# Sensors.net
KiCad netlist of a schematic drawn in Altium Designer
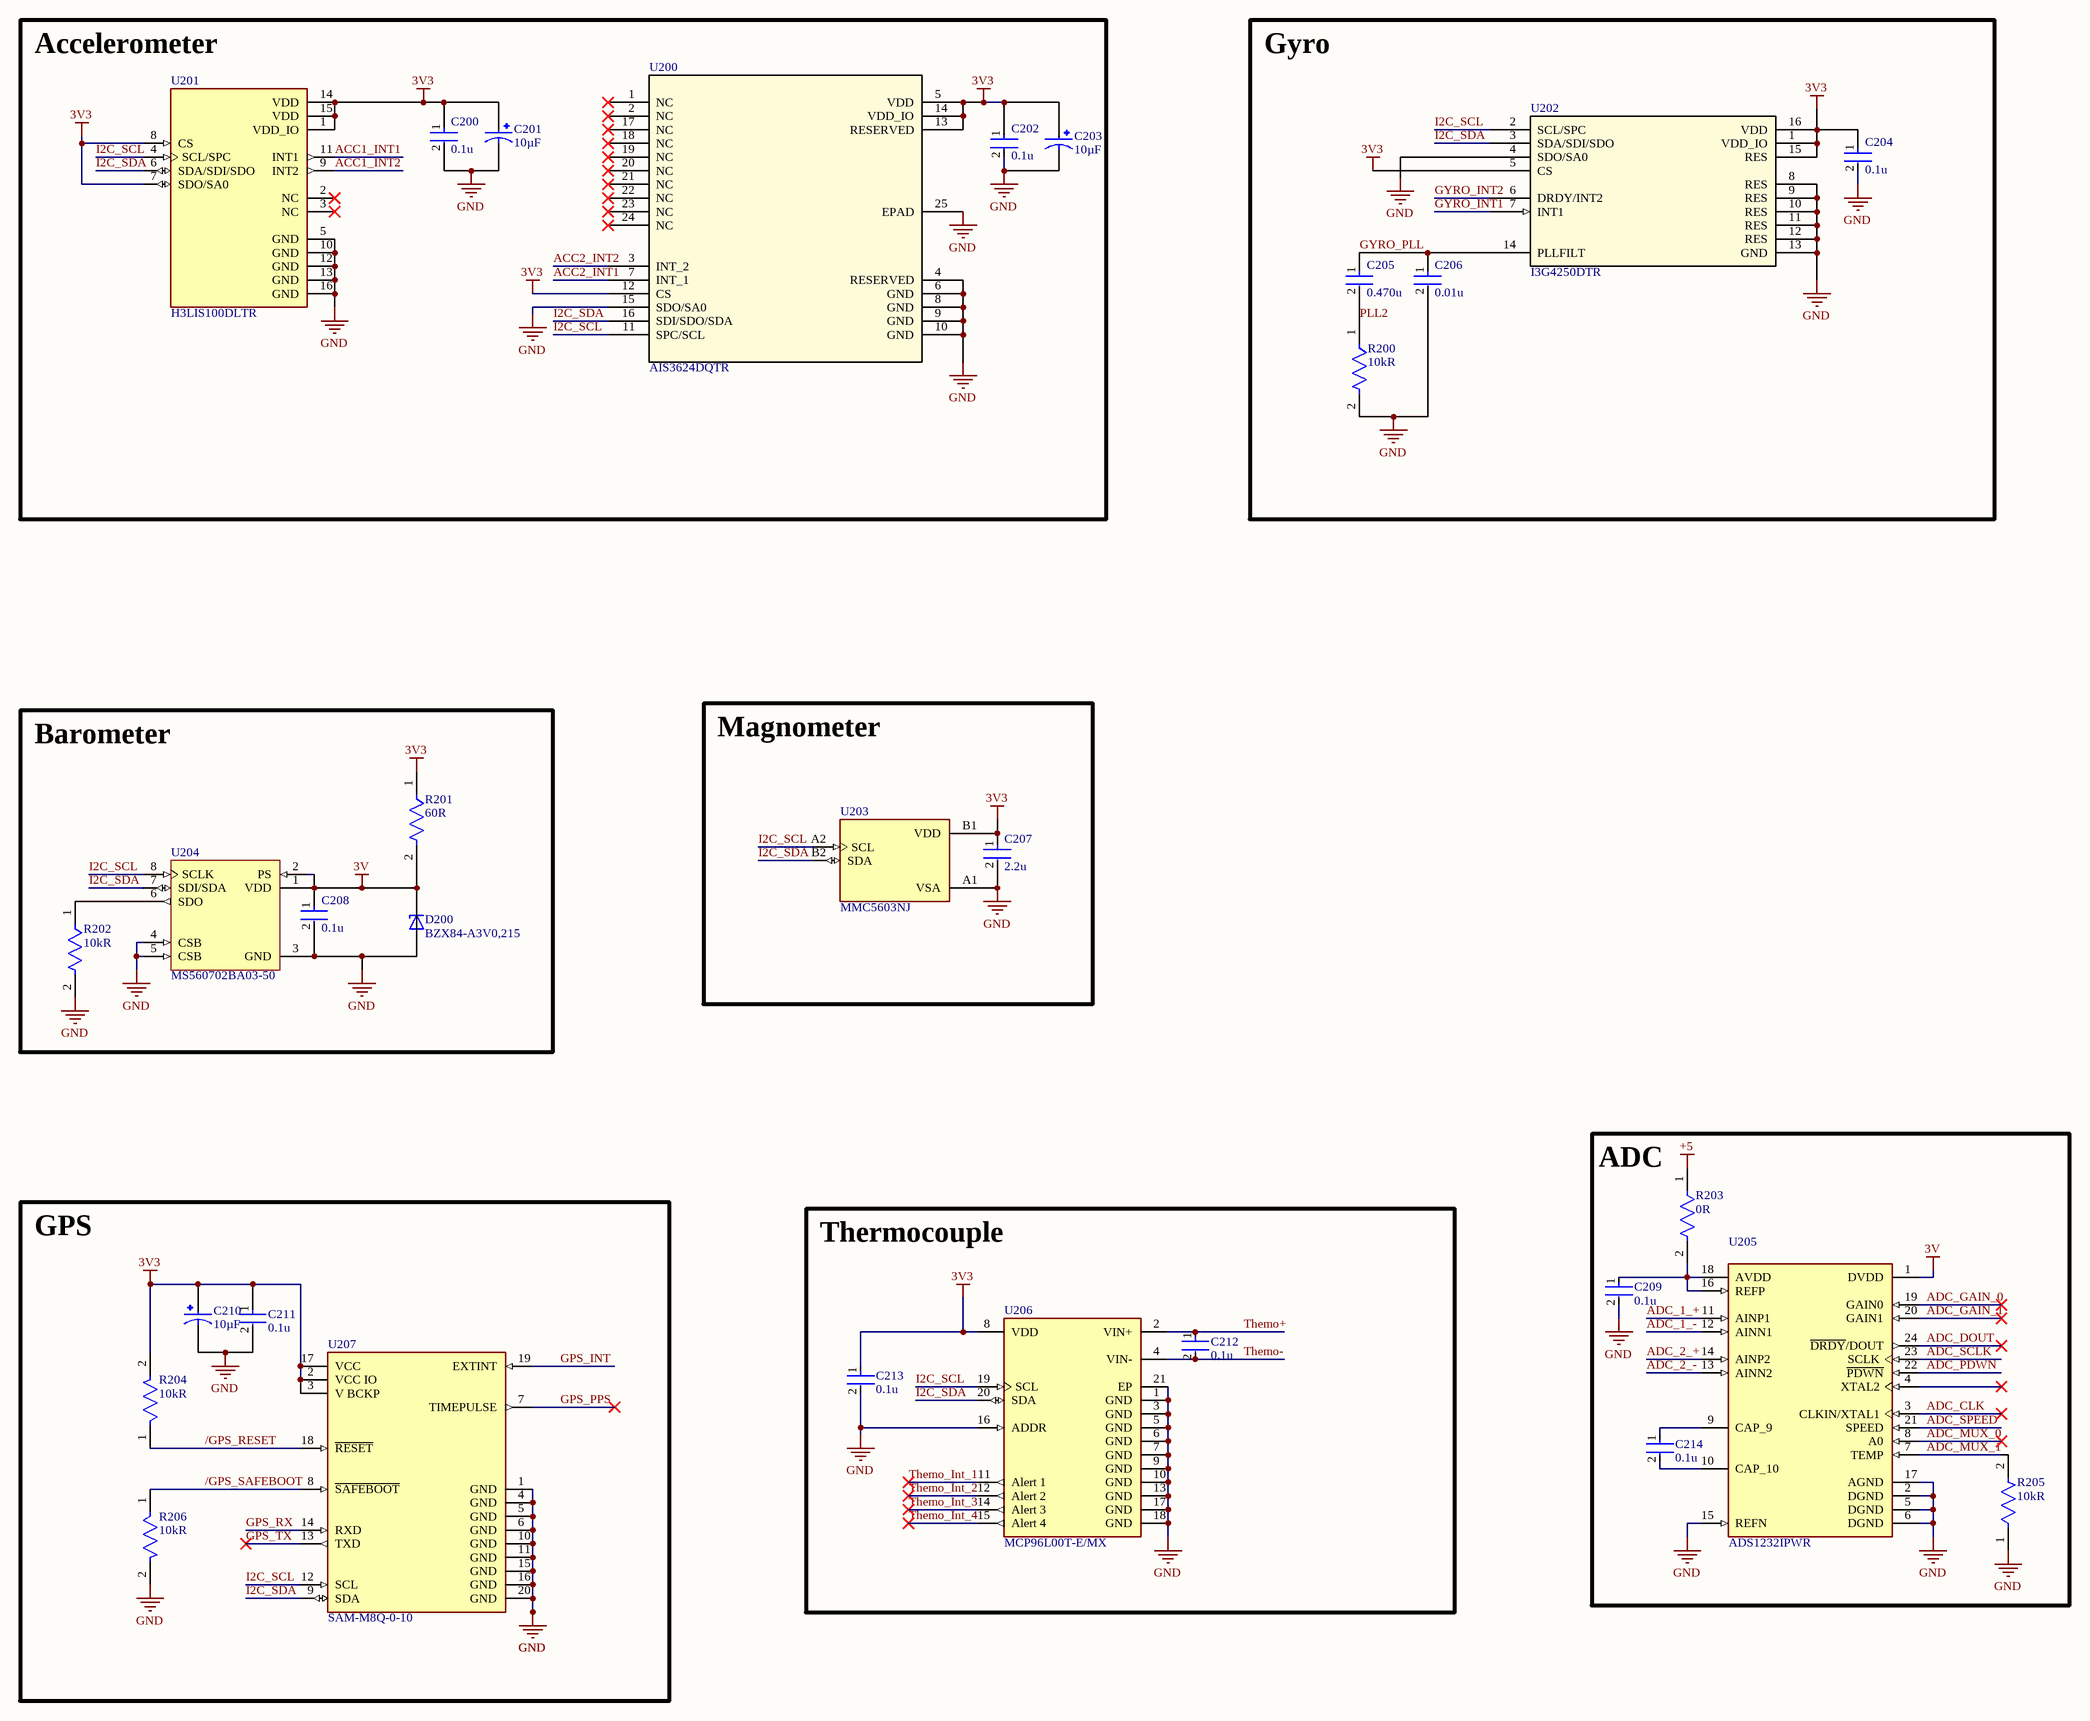
[diagram p0: Sensors.SchDoc]

(export (version "E")
  (design (tool "Eeschema 10.0.6"))
  (components
    (comp (ref "C200")
      (value "CL10C681JB8NFNC")
      (footprint "FP-CL10-IPC_A")
      (description "Cap Ceramic 680pF 50V C0G ±5% Pad SMD 0603 +125°C T/R")
      (fields (field (name "CAPACITANCE") "0.1u") (field (name "TOLERANCE") "5%"))
      (libsource (lib "Altium Content Vault") (part "b4654b650e69147ec39a6b967a45e02"))
    )
    (comp (ref "C201")
      (value "10µF")
      (footprint "CAP_EEEFN1C100R")
      (description "10ÂµF 16V Aluminum Electrolytic Capacitors Radial, Can - SMD 1.35Ohm @ 100kHz 2000 Hrs @ 105Â°C")
      (fields (field (name "DIGI-KEY_PART_NUMBER") "10-EEE-FN1C100RCT-ND") (field (name "MP") "EEEFN1C100R"))
      (libsource (lib "") (part "EEEFN1C100R_1"))
    )
    (comp (ref "C202")
      (value "CL10C681JB8NFNC")
      (footprint "FP-CL10-IPC_A")
      (description "Cap Ceramic 680pF 50V C0G ±5% Pad SMD 0603 +125°C T/R")
      (fields (field (name "CAPACITANCE") "0.1u") (field (name "TOLERANCE") "5%"))
      (libsource (lib "Altium Content Vault") (part "b4654b650e69147ec39a6b967a45e02"))
    )
    (comp (ref "C203")
      (value "10µF")
      (footprint "CAP_EEEFN1C100R")
      (description "10ÂµF 16V Aluminum Electrolytic Capacitors Radial, Can - SMD 1.35Ohm @ 100kHz 2000 Hrs @ 105Â°C")
      (fields (field (name "DIGI-KEY_PART_NUMBER") "10-EEE-FN1C100RCT-ND") (field (name "MP") "EEEFN1C100R"))
      (libsource (lib "") (part "EEEFN1C100R_1"))
    )
    (comp (ref "C204")
      (value "CL10C681JB8NFNC")
      (footprint "FP-CL10-IPC_A")
      (description "Cap Ceramic 680pF 50V C0G ±5% Pad SMD 0603 +125°C T/R")
      (fields (field (name "CAPACITANCE") "0.1u") (field (name "TOLERANCE") "5%"))
      (libsource (lib "Altium Content Vault") (part "b4654b650e69147ec39a6b967a45e02"))
    )
    (comp (ref "C205")
      (value "CL10C681JB8NFNC")
      (footprint "FP-CL10-IPC_A")
      (description "Cap Ceramic 680pF 50V C0G ±5% Pad SMD 0603 +125°C T/R")
      (fields (field (name "CAPACITANCE") "0.470u") (field (name "TOLERANCE") "5%"))
      (libsource (lib "Altium Content Vault") (part "b4654b650e69147ec39a6b967a45e02"))
    )
    (comp (ref "C206")
      (value "CL10C681JB8NFNC")
      (footprint "FP-CL10-IPC_A")
      (description "Cap Ceramic 680pF 50V C0G ±5% Pad SMD 0603 +125°C T/R")
      (fields (field (name "CAPACITANCE") "0.01u") (field (name "TOLERANCE") "5%"))
      (libsource (lib "Altium Content Vault") (part "b4654b650e69147ec39a6b967a45e02"))
    )
    (comp (ref "C207")
      (value "CL10C681JB8NFNC")
      (footprint "FP-CL10-IPC_A")
      (description "Cap Ceramic 680pF 50V C0G ±5% Pad SMD 0603 +125°C T/R")
      (fields (field (name "CAPACITANCE") "2.2u") (field (name "TOLERANCE") "5%"))
      (libsource (lib "Altium Content Vault") (part "b4654b650e69147ec39a6b967a45e02"))
    )
    (comp (ref "C208")
      (value "CL10C681JB8NFNC")
      (footprint "FP-CL10-IPC_A")
      (description "Cap Ceramic 680pF 50V C0G ±5% Pad SMD 0603 +125°C T/R")
      (fields (field (name "CAPACITANCE") "0.1u") (field (name "TOLERANCE") "5%"))
      (libsource (lib "Altium Content Vault") (part "b4654b650e69147ec39a6b967a45e02"))
    )
    (comp (ref "C209")
      (value "CL10C681JB8NFNC")
      (footprint "FP-CL10-IPC_A")
      (description "Cap Ceramic 680pF 50V C0G ±5% Pad SMD 0603 +125°C T/R")
      (fields (field (name "CAPACITANCE") "0.1u") (field (name "TOLERANCE") "5%"))
      (libsource (lib "Altium Content Vault") (part "b4654b650e69147ec39a6b967a45e02"))
    )
    (comp (ref "C210")
      (value "10µF")
      (footprint "CAP_EEEFN1C100R")
      (description "10ÂµF 16V Aluminum Electrolytic Capacitors Radial, Can - SMD 1.35Ohm @ 100kHz 2000 Hrs @ 105Â°C")
      (fields (field (name "DIGI-KEY_PART_NUMBER") "10-EEE-FN1C100RCT-ND") (field (name "MP") "EEEFN1C100R"))
      (libsource (lib "Erich Robb") (part "EEEFN1C100R"))
    )
    (comp (ref "C211")
      (value "CL10C681JB8NFNC")
      (footprint "FP-CL10-IPC_A")
      (description "Cap Ceramic 680pF 50V C0G ±5% Pad SMD 0603 +125°C T/R")
      (fields (field (name "CAPACITANCE") "0.1u") (field (name "TOLERANCE") "5%"))
      (libsource (lib "Altium Content Vault") (part "b4654b650e69147ec39a6b967a45e02"))
    )
    (comp (ref "C212")
      (value "CL10C681JB8NFNC")
      (footprint "FP-CL10-IPC_A")
      (description "Cap Ceramic 680pF 50V C0G ±5% Pad SMD 0603 +125°C T/R")
      (fields (field (name "CAPACITANCE") "0.1u") (field (name "TOLERANCE") "5%"))
      (libsource (lib "Altium Content Vault") (part "b4654b650e69147ec39a6b967a45e02"))
    )
    (comp (ref "C213")
      (value "CL10C681JB8NFNC")
      (footprint "FP-CL10-IPC_A")
      (description "Cap Ceramic 680pF 50V C0G ±5% Pad SMD 0603 +125°C T/R")
      (fields (field (name "CAPACITANCE") "0.1u") (field (name "TOLERANCE") "5%"))
      (libsource (lib "Altium Content Vault") (part "b4654b650e69147ec39a6b967a45e02"))
    )
    (comp (ref "C214")
      (value "CL10C681JB8NFNC")
      (footprint "FP-CL10-IPC_A")
      (description "Cap Ceramic 680pF 50V C0G ±5% Pad SMD 0603 +125°C T/R")
      (fields (field (name "CAPACITANCE") "0.1u") (field (name "TOLERANCE") "5%"))
      (libsource (lib "Altium Content Vault") (part "b4654b650e69147ec39a6b967a45e02"))
    )
    (comp (ref "D200")
      (value "BZX84-A3V0,215")
      (footprint "SOT95P230X110-3N")
      (description "Zener Diode 3 V 250 mW Â±1% Surface Mount TO-236AB")
      (fields (field (name "MF") "Nexperia"))
      (libsource (lib "Erich Robb") (part "BZX84-C3V0,215"))
    )
    (comp (ref "R200")
      (value "10kR")
      (footprint "FP-CPF0603-MFG")
      (description "RES SMD 2.15KΩ 0.1% 1/16W 0603")
      (fields
        (field (name "MANUFACTURER") "TE Connectivity")
        (field (name "OCTOPART") "https://octopart.com/cpf0603b2k15e1-te+connectivity-22739551")
      )
      (libsource (lib "Altium Content Vault") (part "1029c3af85768c4190bb7ad29bc67b5"))
    )
    (comp (ref "R201")
      (value "60R")
      (footprint "FP-CPF0603-MFG")
      (description "RES SMD 2.15KΩ 0.1% 1/16W 0603")
      (fields
        (field (name "MANUFACTURER") "TE Connectivity")
        (field (name "OCTOPART") "https://octopart.com/cpf0603b2k15e1-te+connectivity-22739551")
      )
      (libsource (lib "Altium Content Vault") (part "1029c3af85768c4190bb7ad29bc67b5"))
    )
    (comp (ref "R202")
      (value "10kR")
      (footprint "FP-CPF0603-MFG")
      (description "RES SMD 2.15KΩ 0.1% 1/16W 0603")
      (fields
        (field (name "MANUFACTURER") "TE Connectivity")
        (field (name "OCTOPART") "https://octopart.com/cpf0603b2k15e1-te+connectivity-22739551")
      )
      (libsource (lib "Altium Content Vault") (part "1029c3af85768c4190bb7ad29bc67b5"))
    )
    (comp (ref "R203")
      (value "0R")
      (footprint "FP-CPF0603-MFG")
      (description "RES SMD 2.15KΩ 0.1% 1/16W 0603")
      (fields
        (field (name "MANUFACTURER") "TE Connectivity")
        (field (name "OCTOPART") "https://octopart.com/cpf0603b2k15e1-te+connectivity-22739551")
      )
      (libsource (lib "Altium Content Vault") (part "1029c3af85768c4190bb7ad29bc67b5"))
    )
    (comp (ref "R204")
      (value "10kR")
      (footprint "FP-CPF0603-MFG")
      (description "RES SMD 2.15KΩ 0.1% 1/16W 0603")
      (fields
        (field (name "MANUFACTURER") "TE Connectivity")
        (field (name "OCTOPART") "https://octopart.com/cpf0603b2k15e1-te+connectivity-22739551")
      )
      (libsource (lib "Altium Content Vault") (part "1029c3af85768c4190bb7ad29bc67b5"))
    )
    (comp (ref "R205")
      (value "10kR")
      (footprint "FP-CPF0603-MFG")
      (description "RES SMD 2.15KΩ 0.1% 1/16W 0603")
      (fields
        (field (name "MANUFACTURER") "TE Connectivity")
        (field (name "OCTOPART") "https://octopart.com/cpf0603b2k15e1-te+connectivity-22739551")
      )
      (libsource (lib "Altium Content Vault") (part "1029c3af85768c4190bb7ad29bc67b5"))
    )
    (comp (ref "R206")
      (value "10kR")
      (footprint "FP-CPF0603-MFG")
      (description "RES SMD 2.15KΩ 0.1% 1/16W 0603")
      (fields
        (field (name "MANUFACTURER") "TE Connectivity")
        (field (name "OCTOPART") "https://octopart.com/cpf0603b2k15e1-te+connectivity-22739551")
      )
      (libsource (lib "Altium Content Vault") (part "1029c3af85768c4190bb7ad29bc67b5"))
    )
    (comp (ref "U200")
      (value "AIS3624DQTR")
      (footprint "QFN24L_4X4X0P5_STM")
      (description "No Description Available")
      (libsource (lib "Erich Robb") (part "AIS3624DQTR"))
    )
    (comp (ref "U201")
      (value "H3LIS100DLTR")
      (footprint "PQFN50P300X300X100-16N")
      (description "Accelerometer X, Y, Z Axis Â±100g 25Hz ~ 200Hz 16-TFLGA (3x3)")
      (fields (field (name "MF") "STMicroelectronics"))
      (libsource (lib "Erich Robb") (part "H3LIS100DLTR"))
    )
    (comp (ref "U202")
      (value "I3G4250DTR")
      (footprint "LGA-16_4X4X1_STM")
      (description "No Description Available")
      (libsource (lib "Erich Robb") (part "I3G4250DTR"))
    )
    (comp (ref "U203")
      (value "MMC5603NJ")
      (footprint "XDCR_MMC5603NJ")
      (description "Magnetoresistive Sensor X, Y, Z Axis 4-WLP (0.82x0.82)")
      (fields (field (name "MF") "Memsic Inc."))
      (libsource (lib "Erich Robb") (part "MMC5603NJ"))
    )
    (comp (ref "U204")
      (value "MS560702BA03-50")
      (footprint "TECO-MS560702BA03-50_V")
      (description "Absolute, 4.35Psi Min, 15.95Psi Max, 0-3V, Rectangular, Surface Mount")
      (libsource (lib "Colin Sutter") (part "TECO-MS560702BA03-8"))
    )
    (comp (ref "U205")
      (value "ADS1232IPWR")
      (footprint "SOP65P640X120-24N")
      (fields (field (name "MF") "{'manufacturer': u'Texas Instruments'}"))
      (libsource (lib "Colin Sutter") (part "ADS1232IPWR"))
    )
    (comp (ref "U206")
      (value "MCP96L00T-E/MX")
      (footprint "FP-C04-186-IPC_C")
      (description "+/- 4.0C THERMOCOUPLE TO I2C CON")
      (libsource (lib "Altium Content Vault") (part "7f964d83eff93ee89ee50805eef2d84"))
    )
    (comp (ref "U207")
      (value "SAM-M8Q-0-10")
      (footprint "FP-SAM-M8Q-0-10-MFG")
      (description "RF RX GALILEO 1.575GHZ/1.602GHZ")
      (fields
        (field (name "MANUFACTURER") "uBlox")
        (field (name "OCTOPART") "https://octopart.com/sam-m8q-0-10-u-blox-88247750")
      )
      (libsource (lib "Altium Content Vault") (part "e897669bc61729ed63f6e62e0b1e840"))
    )
  )
  (nets
    (net (code "1") (name "+5") (class "Default")
      (node (ref "R203") (pin "1") (pinfunction "1_1") (pintype "passive"))
    )
    (net (code "2") (name "/ACC1_INT1") (class "Default")
      (node (ref "U201") (pin "11") (pinfunction "INT1_11") (pintype "output"))
    )
    (net (code "3") (name "/ACC1_INT2") (class "Default")
      (node (ref "U201") (pin "9") (pinfunction "INT2_9") (pintype "output"))
    )
    (net (code "4") (name "/ACC2_INT1") (class "Default")
      (node (ref "U200") (pin "7") (pinfunction "INT_1_7") (pintype "passive"))
    )
    (net (code "5") (name "/ACC2_INT2") (class "Default")
      (node (ref "U200") (pin "3") (pinfunction "INT_2_3") (pintype "passive"))
    )
    (net (code "6") (name "/ADC_1_+") (class "Default")
      (node (ref "U205") (pin "11") (pinfunction "AINP1_11") (pintype "input"))
    )
    (net (code "7") (name "/ADC_1_-") (class "Default")
      (node (ref "U205") (pin "12") (pinfunction "AINN1_12") (pintype "input"))
    )
    (net (code "8") (name "/ADC_2_+") (class "Default")
      (node (ref "U205") (pin "14") (pinfunction "AINP2_14") (pintype "input"))
    )
    (net (code "9") (name "/ADC_2_-") (class "Default")
      (node (ref "U205") (pin "13") (pinfunction "AINN2_13") (pintype "input"))
    )
    (net (code "10") (name "/ADC_CLK") (class "Default")
      (node (ref "U205") (pin "3") (pinfunction "CLKIN/XTAL1_3") (pintype "input+no_connect"))
    )
    (net (code "11") (name "/ADC_DOUT") (class "Default")
      (node (ref "U205") (pin "24") (pinfunction "~{DRDY}/DOUT_24") (pintype "output+no_connect"))
    )
    (net (code "12") (name "/ADC_GAIN_0") (class "Default")
      (node (ref "U205") (pin "19") (pinfunction "GAIN0_19") (pintype "input+no_connect"))
    )
    (net (code "13") (name "/ADC_GAIN_1") (class "Default")
      (node (ref "U205") (pin "20") (pinfunction "GAIN1_20") (pintype "input+no_connect"))
    )
    (net (code "14") (name "/ADC_MUX_0") (class "Default")
      (node (ref "U205") (pin "8") (pinfunction "A0_8") (pintype "input+no_connect"))
    )
    (net (code "15") (name "/ADC_MUX_1") (class "Default")
      (node (ref "R205") (pin "2") (pinfunction "2_2") (pintype "passive"))
      (node (ref "U205") (pin "7") (pinfunction "TEMP_7") (pintype "input"))
    )
    (net (code "16") (name "/ADC_PDWN") (class "Default")
      (node (ref "U205") (pin "22") (pinfunction "~{PDWN}_22") (pintype "input"))
    )
    (net (code "17") (name "/ADC_SCLK") (class "Default")
      (node (ref "U205") (pin "23") (pinfunction "SCLK_23") (pintype "input"))
    )
    (net (code "18") (name "/ADC_SPEED") (class "Default")
      (node (ref "U205") (pin "21") (pinfunction "SPEED_21") (pintype "input"))
    )
    (net (code "19") (name "/GPS_INT") (class "Default")
      (node (ref "U207") (pin "19") (pinfunction "EXTINT_19") (pintype "input"))
    )
    (net (code "20") (name "/GPS_PPS") (class "Default")
      (node (ref "U207") (pin "7") (pinfunction "TIMEPULSE_7") (pintype "output+no_connect"))
    )
    (net (code "21") (name "/GPS_RX") (class "Default")
      (node (ref "U207") (pin "14") (pinfunction "RXD_14") (pintype "input"))
    )
    (net (code "22") (name "/GPS_TX") (class "Default")
      (node (ref "U207") (pin "13") (pinfunction "TXD_13") (pintype "output+no_connect"))
    )
    (net (code "23") (name "/GYRO_INT1") (class "Default")
      (node (ref "U202") (pin "7") (pinfunction "INT1_7") (pintype "input"))
    )
    (net (code "24") (name "/GYRO_INT2") (class "Default")
      (node (ref "U202") (pin "6") (pinfunction "DRDY/INT2_6") (pintype "passive"))
    )
    (net (code "25") (name "/GYRO_PLL") (class "Default")
      (node (ref "C205") (pin "1") (pinfunction "1_1") (pintype "passive"))
      (node (ref "C206") (pin "1") (pinfunction "1_1") (pintype "passive"))
      (node (ref "U202") (pin "14") (pinfunction "PLLFILT_14") (pintype "passive"))
    )
    (net (code "26") (name "/I2C_SCL") (class "Default")
      (node (ref "U200") (pin "11") (pinfunction "SPC/SCL_11") (pintype "passive"))
      (node (ref "U201") (pin "4") (pinfunction "SCL/SPC_4") (pintype "input"))
      (node (ref "U202") (pin "2") (pinfunction "SCL/SPC_2") (pintype "passive"))
      (node (ref "U203") (pin "A2") (pinfunction "SCL_A2") (pintype "input"))
      (node (ref "U204") (pin "8") (pinfunction "SCLK_8") (pintype "input"))
      (node (ref "U206") (pin "19") (pinfunction "SCL_19") (pintype "input"))
      (node (ref "U207") (pin "12") (pinfunction "SCL_12") (pintype "input"))
    )
    (net (code "27") (name "/I2C_SDA") (class "Default")
      (node (ref "U200") (pin "16") (pinfunction "SDI/SDO/SDA_16") (pintype "passive"))
      (node (ref "U201") (pin "6") (pinfunction "SDA/SDI/SDO_6") (pintype "bidirectional"))
      (node (ref "U202") (pin "3") (pinfunction "SDA/SDI/SDO_3") (pintype "passive"))
      (node (ref "U203") (pin "B2") (pinfunction "SDA_B2") (pintype "bidirectional"))
      (node (ref "U204") (pin "7") (pinfunction "SDI/SDA_7") (pintype "bidirectional"))
      (node (ref "U206") (pin "20") (pinfunction "SDA_20") (pintype "bidirectional"))
      (node (ref "U207") (pin "9") (pinfunction "SDA_9") (pintype "bidirectional"))
    )
    (net (code "28") (name "/PLL2") (class "Default")
      (node (ref "C205") (pin "2") (pinfunction "2_2") (pintype "passive"))
      (node (ref "R200") (pin "1") (pinfunction "1_1") (pintype "passive"))
    )
    (net (code "29") (name "/Themo+") (class "Default")
      (node (ref "C212") (pin "1") (pinfunction "1_1") (pintype "passive"))
      (node (ref "U206") (pin "2") (pinfunction "VIN+_2") (pintype "power_in"))
    )
    (net (code "30") (name "/Themo-") (class "Default")
      (node (ref "C212") (pin "2") (pinfunction "2_2") (pintype "passive"))
      (node (ref "U206") (pin "4") (pinfunction "VIN-_4") (pintype "power_in"))
    )
    (net (code "31") (name "/Themo_Int_1") (class "Default")
      (node (ref "U206") (pin "11") (pinfunction "Alert_1_11") (pintype "output+no_connect"))
    )
    (net (code "32") (name "/Themo_Int_2") (class "Default")
      (node (ref "U206") (pin "12") (pinfunction "Alert_2_12") (pintype "output+no_connect"))
    )
    (net (code "33") (name "/Themo_Int_3") (class "Default")
      (node (ref "U206") (pin "14") (pinfunction "Alert_3_14") (pintype "output+no_connect"))
    )
    (net (code "34") (name "/Themo_Int_4") (class "Default")
      (node (ref "U206") (pin "15") (pinfunction "Alert_4_15") (pintype "output+no_connect"))
    )
    (net (code "35") (name "/{slash}GPS_RESET") (class "Default")
      (node (ref "R204") (pin "1") (pinfunction "1_1") (pintype "passive"))
      (node (ref "U207") (pin "18") (pinfunction "~{RESET}_18") (pintype "input"))
    )
    (net (code "36") (name "/{slash}GPS_SAFEBOOT") (class "Default")
      (node (ref "R206") (pin "1") (pinfunction "1_1") (pintype "passive"))
      (node (ref "U207") (pin "8") (pinfunction "~{SAFEBOOT}_8") (pintype "input"))
    )
    (net (code "37") (name "3V") (class "Default")
      (node (ref "C208") (pin "1") (pinfunction "1_1") (pintype "passive"))
      (node (ref "D200") (pin "3") (pinfunction "C_3") (pintype "passive"))
      (node (ref "R201") (pin "2") (pinfunction "2_2") (pintype "passive"))
      (node (ref "U204") (pin "1") (pinfunction "VDD_1") (pintype "power_in"))
      (node (ref "U204") (pin "2") (pinfunction "PS_2") (pintype "input"))
      (node (ref "U205") (pin "1") (pinfunction "DVDD_1") (pintype "power_in"))
    )
    (net (code "38") (name "3V3") (class "Default")
      (node (ref "C200") (pin "1") (pinfunction "1_1") (pintype "passive"))
      (node (ref "C201") (pin "1") (pinfunction "1_1") (pintype "passive"))
      (node (ref "C202") (pin "1") (pinfunction "1_1") (pintype "passive"))
      (node (ref "C203") (pin "1") (pinfunction "1_1") (pintype "passive"))
      (node (ref "C204") (pin "1") (pinfunction "1_1") (pintype "passive"))
      (node (ref "C207") (pin "1") (pinfunction "1_1") (pintype "passive"))
      (node (ref "C210") (pin "1") (pinfunction "1_1") (pintype "passive"))
      (node (ref "C211") (pin "1") (pinfunction "1_1") (pintype "passive"))
      (node (ref "C213") (pin "1") (pinfunction "1_1") (pintype "passive"))
      (node (ref "R201") (pin "1") (pinfunction "1_1") (pintype "passive"))
      (node (ref "R204") (pin "2") (pinfunction "2_2") (pintype "passive"))
      (node (ref "U200") (pin "12") (pinfunction "CS_12") (pintype "passive"))
      (node (ref "U200") (pin "13") (pinfunction "RESERVED_13") (pintype "passive"))
      (node (ref "U200") (pin "14") (pinfunction "VDD_IO_14") (pintype "passive"))
      (node (ref "U200") (pin "5") (pinfunction "VDD_5") (pintype "passive"))
      (node (ref "U201") (pin "1") (pinfunction "VDD_IO_1") (pintype "power_in"))
      (node (ref "U201") (pin "14") (pinfunction "VDD_14") (pintype "power_in"))
      (node (ref "U201") (pin "15") (pinfunction "VDD_15") (pintype "power_in"))
      (node (ref "U201") (pin "7") (pinfunction "SDO/SA0_7") (pintype "bidirectional"))
      (node (ref "U201") (pin "8") (pinfunction "CS_8") (pintype "input"))
      (node (ref "U202") (pin "1") (pinfunction "VDD_IO_1") (pintype "power_in"))
      (node (ref "U202") (pin "15") (pinfunction "RES_15") (pintype "power_in"))
      (node (ref "U202") (pin "16") (pinfunction "VDD_16") (pintype "power_in"))
      (node (ref "U202") (pin "5") (pinfunction "CS_5") (pintype "passive"))
      (node (ref "U203") (pin "B1") (pinfunction "VDD_B1") (pintype "power_in"))
      (node (ref "U206") (pin "8") (pinfunction "VDD_8") (pintype "power_in"))
      (node (ref "U207") (pin "17") (pinfunction "VCC_17") (pintype "power_in"))
      (node (ref "U207") (pin "2") (pinfunction "VCC_IO_2") (pintype "power_in"))
      (node (ref "U207") (pin "3") (pinfunction "V_BCKP_3") (pintype "power_in"))
    )
    (net (code "39") (name "GND") (class "Default")
      (node (ref "C200") (pin "2") (pinfunction "2_2") (pintype "passive"))
      (node (ref "C201") (pin "2") (pinfunction "2_2") (pintype "passive"))
      (node (ref "C202") (pin "2") (pinfunction "2_2") (pintype "passive"))
      (node (ref "C203") (pin "2") (pinfunction "2_2") (pintype "passive"))
      (node (ref "C204") (pin "2") (pinfunction "2_2") (pintype "passive"))
      (node (ref "C206") (pin "2") (pinfunction "2_2") (pintype "passive"))
      (node (ref "C207") (pin "2") (pinfunction "2_2") (pintype "passive"))
      (node (ref "C208") (pin "2") (pinfunction "2_2") (pintype "passive"))
      (node (ref "C209") (pin "2") (pinfunction "2_2") (pintype "passive"))
      (node (ref "C210") (pin "2") (pinfunction "2_2") (pintype "passive"))
      (node (ref "C211") (pin "2") (pinfunction "2_2") (pintype "passive"))
      (node (ref "C213") (pin "2") (pinfunction "2_2") (pintype "passive"))
      (node (ref "D200") (pin "1") (pinfunction "A_1") (pintype "passive"))
      (node (ref "R200") (pin "2") (pinfunction "2_2") (pintype "passive"))
      (node (ref "R202") (pin "2") (pinfunction "2_2") (pintype "passive"))
      (node (ref "R205") (pin "1") (pinfunction "1_1") (pintype "passive"))
      (node (ref "R206") (pin "2") (pinfunction "2_2") (pintype "passive"))
      (node (ref "U200") (pin "10") (pinfunction "GND_10") (pintype "power_in"))
      (node (ref "U200") (pin "15") (pinfunction "SDO/SA0_15") (pintype "passive"))
      (node (ref "U200") (pin "25") (pinfunction "EPAD_25") (pintype "power_in"))
      (node (ref "U200") (pin "4") (pinfunction "RESERVED_4") (pintype "power_in"))
      (node (ref "U200") (pin "6") (pinfunction "GND_6") (pintype "power_in"))
      (node (ref "U200") (pin "8") (pinfunction "GND_8") (pintype "power_in"))
      (node (ref "U200") (pin "9") (pinfunction "GND_9") (pintype "power_in"))
      (node (ref "U201") (pin "10") (pinfunction "GND_10") (pintype "power_in"))
      (node (ref "U201") (pin "12") (pinfunction "GND_12") (pintype "power_in"))
      (node (ref "U201") (pin "13") (pinfunction "GND_13") (pintype "power_in"))
      (node (ref "U201") (pin "16") (pinfunction "GND_16") (pintype "power_in"))
      (node (ref "U201") (pin "5") (pinfunction "GND_5") (pintype "power_in"))
      (node (ref "U202") (pin "10") (pinfunction "RES_10") (pintype "power_in"))
      (node (ref "U202") (pin "11") (pinfunction "RES_11") (pintype "power_in"))
      (node (ref "U202") (pin "12") (pinfunction "RES_12") (pintype "power_in"))
      (node (ref "U202") (pin "13") (pinfunction "GND_13") (pintype "power_in"))
      (node (ref "U202") (pin "4") (pinfunction "SDO/SA0_4") (pintype "passive"))
      (node (ref "U202") (pin "8") (pinfunction "RES_8") (pintype "power_in"))
      (node (ref "U202") (pin "9") (pinfunction "RES_9") (pintype "power_in"))
      (node (ref "U203") (pin "A1") (pinfunction "VSA_A1") (pintype "power_in"))
      (node (ref "U204") (pin "3") (pinfunction "GND_3") (pintype "power_in"))
      (node (ref "U204") (pin "4") (pinfunction "CSB_4") (pintype "input"))
      (node (ref "U204") (pin "5") (pinfunction "CSB_5") (pintype "input"))
      (node (ref "U205") (pin "15") (pinfunction "REFN_15") (pintype "input"))
      (node (ref "U205") (pin "17") (pinfunction "AGND_17") (pintype "power_in"))
      (node (ref "U205") (pin "2") (pinfunction "DGND_2") (pintype "power_in"))
      (node (ref "U205") (pin "5") (pinfunction "DGND_5") (pintype "power_in"))
      (node (ref "U205") (pin "6") (pinfunction "DGND_6") (pintype "power_in"))
      (node (ref "U206") (pin "1") (pinfunction "GND_1") (pintype "power_in"))
      (node (ref "U206") (pin "10") (pinfunction "GND_10") (pintype "power_in"))
      (node (ref "U206") (pin "13") (pinfunction "GND_13") (pintype "power_in"))
      (node (ref "U206") (pin "16") (pinfunction "ADDR_16") (pintype "input"))
      (node (ref "U206") (pin "17") (pinfunction "GND_17") (pintype "power_in"))
      (node (ref "U206") (pin "18") (pinfunction "GND_18") (pintype "power_in"))
      (node (ref "U206") (pin "21") (pinfunction "EP_21") (pintype "power_in"))
      (node (ref "U206") (pin "3") (pinfunction "GND_3") (pintype "power_in"))
      (node (ref "U206") (pin "5") (pinfunction "GND_5") (pintype "power_in"))
      (node (ref "U206") (pin "6") (pinfunction "GND_6") (pintype "power_in"))
      (node (ref "U206") (pin "7") (pinfunction "GND_7") (pintype "power_in"))
      (node (ref "U206") (pin "9") (pinfunction "GND_9") (pintype "power_in"))
      (node (ref "U207") (pin "1") (pinfunction "GND_1") (pintype "power_in"))
      (node (ref "U207") (pin "10") (pinfunction "GND_10") (pintype "power_in"))
      (node (ref "U207") (pin "11") (pinfunction "GND_11") (pintype "power_in"))
      (node (ref "U207") (pin "15") (pinfunction "GND_15") (pintype "power_in"))
      (node (ref "U207") (pin "16") (pinfunction "GND_16") (pintype "power_in"))
      (node (ref "U207") (pin "20") (pinfunction "GND_20") (pintype "power_in"))
      (node (ref "U207") (pin "4") (pinfunction "GND_4") (pintype "power_in"))
      (node (ref "U207") (pin "5") (pinfunction "GND_5") (pintype "power_in"))
      (node (ref "U207") (pin "6") (pinfunction "GND_6") (pintype "power_in"))
    )
    (net (code "40") (name "Net-(U204-SDO)") (class "Default")
      (node (ref "R202") (pin "1") (pinfunction "1_1") (pintype "passive"))
      (node (ref "U204") (pin "6") (pinfunction "SDO_6") (pintype "output"))
    )
    (net (code "41") (name "Net-(U205-AVDD)") (class "Default")
      (node (ref "C209") (pin "1") (pinfunction "1_1") (pintype "passive"))
      (node (ref "R203") (pin "2") (pinfunction "2_2") (pintype "passive"))
      (node (ref "U205") (pin "16") (pinfunction "REFP_16") (pintype "input"))
      (node (ref "U205") (pin "18") (pinfunction "AVDD_18") (pintype "power_in"))
    )
    (net (code "42") (name "Net-(U205-CAP_9)") (class "Default")
      (node (ref "C214") (pin "1") (pinfunction "1_1") (pintype "passive"))
      (node (ref "U205") (pin "9") (pinfunction "CAP_9_9") (pintype "passive"))
    )
    (net (code "43") (name "Net-(U205-CAP_10)") (class "Default")
      (node (ref "C214") (pin "2") (pinfunction "2_2") (pintype "passive"))
      (node (ref "U205") (pin "10") (pinfunction "CAP_10_10") (pintype "passive"))
    )
    (net (code "44") (name "unconnected-(U200-NC-Pad1)") (class "Default")
      (node (ref "U200") (pin "1") (pinfunction "NC_1") (pintype "passive+no_connect"))
    )
    (net (code "45") (name "unconnected-(U200-NC-Pad2)") (class "Default")
      (node (ref "U200") (pin "2") (pinfunction "NC_2") (pintype "passive+no_connect"))
    )
    (net (code "46") (name "unconnected-(U200-NC-Pad17)") (class "Default")
      (node (ref "U200") (pin "17") (pinfunction "NC_17") (pintype "passive+no_connect"))
    )
    (net (code "47") (name "unconnected-(U200-NC-Pad18)") (class "Default")
      (node (ref "U200") (pin "18") (pinfunction "NC_18") (pintype "passive+no_connect"))
    )
    (net (code "48") (name "unconnected-(U200-NC-Pad19)") (class "Default")
      (node (ref "U200") (pin "19") (pinfunction "NC_19") (pintype "passive+no_connect"))
    )
    (net (code "49") (name "unconnected-(U200-NC-Pad20)") (class "Default")
      (node (ref "U200") (pin "20") (pinfunction "NC_20") (pintype "passive+no_connect"))
    )
    (net (code "50") (name "unconnected-(U200-NC-Pad21)") (class "Default")
      (node (ref "U200") (pin "21") (pinfunction "NC_21") (pintype "passive+no_connect"))
    )
    (net (code "51") (name "unconnected-(U200-NC-Pad22)") (class "Default")
      (node (ref "U200") (pin "22") (pinfunction "NC_22") (pintype "passive+no_connect"))
    )
    (net (code "52") (name "unconnected-(U200-NC-Pad23)") (class "Default")
      (node (ref "U200") (pin "23") (pinfunction "NC_23") (pintype "passive+no_connect"))
    )
    (net (code "53") (name "unconnected-(U200-NC-Pad24)") (class "Default")
      (node (ref "U200") (pin "24") (pinfunction "NC_24") (pintype "passive+no_connect"))
    )
    (net (code "54") (name "unconnected-(U201-NC-Pad2)") (class "Default")
      (node (ref "U201") (pin "2") (pinfunction "NC_2") (pintype "passive+no_connect"))
    )
    (net (code "55") (name "unconnected-(U201-NC-Pad3)") (class "Default")
      (node (ref "U201") (pin "3") (pinfunction "NC_3") (pintype "passive+no_connect"))
    )
    (net (code "56") (name "unconnected-(U205-XTAL2-Pad4)") (class "Default")
      (node (ref "U205") (pin "4") (pinfunction "XTAL2_4") (pintype "input+no_connect"))
    )
  )
)
